# 02-_-.net
KiCad netlist of a schematic drawn in Altium Designer
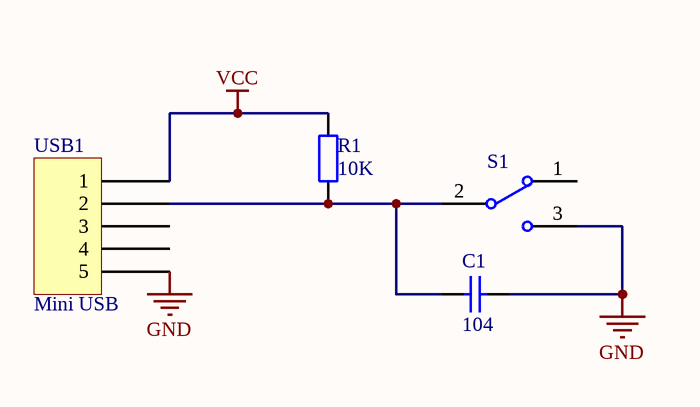
[diagram p0: 02-碰撞模块-原理图.SchDoc]

(export (version "E")
  (design (tool "Eeschema 10.0.6"))
  (components
    (comp (ref "C1")
      (value "104")
      (footprint "0805")
      (description "Capacitor")
      (fields (field (name "Comment") "Cap") (field (name "PUBLISHER") "Altium Limited"))
      (libsource (lib "Miscellaneous Devices") (part "Cap"))
    )
    (comp (ref "R1")
      (value "10K")
      (footprint "0805")
      (description "Resistor")
      (fields (field (name "Comment") "Res2") (field (name "PUBLISHER") "Altium Limited"))
      (libsource (lib "Miscellaneous Devices") (part "Res2"))
    )
    (comp (ref "S1")
      (value "SW-SPDT")
      (footprint "key")
      (description "SPDT Subminiature Toggle Switch, Right Angle Mounting, Vertical Actuation")
      (fields (field (name "PUBLISHER") "Altium Limited"))
      (libsource (lib "Miscellaneous Devices") (part "SW-SPDT"))
    )
    (comp (ref "USB1")
      (value "Mini USB")
      (footprint "USB/SM0.8-6H5")
      (libsource (lib "Schlib1") (part "Mini USB"))
    )
  )
  (nets
    (net (code "1") (name "GND") (class "Default")
      (node (ref "C1") (pin "1") (pinfunction "1_1") (pintype "passive"))
      (node (ref "S1") (pin "3") (pinfunction "3_3") (pintype "passive"))
      (node (ref "USB1") (pin "5") (pinfunction "5_5") (pintype "passive"))
    )
    (net (code "2") (name "Net-(C1-Pad2)") (class "Default")
      (node (ref "C1") (pin "2") (pinfunction "2_2") (pintype "passive"))
      (node (ref "R1") (pin "2") (pinfunction "2_2") (pintype "passive"))
      (node (ref "S1") (pin "2") (pinfunction "2_2") (pintype "passive"))
      (node (ref "USB1") (pin "2") (pinfunction "2_2") (pintype "passive"))
    )
    (net (code "3") (name "VCC") (class "Default")
      (node (ref "R1") (pin "1") (pinfunction "1_1") (pintype "passive"))
      (node (ref "USB1") (pin "1") (pinfunction "1_1") (pintype "passive"))
    )
    (net (code "4") (name "unconnected-(S1-Pad1)") (class "Default")
      (node (ref "S1") (pin "1") (pinfunction "1_1") (pintype "passive"))
    )
    (net (code "5") (name "unconnected-(USB1-Pad3)") (class "Default")
      (node (ref "USB1") (pin "3") (pinfunction "3_3") (pintype "passive"))
    )
    (net (code "6") (name "unconnected-(USB1-Pad4)") (class "Default")
      (node (ref "USB1") (pin "4") (pinfunction "4_4") (pintype "passive"))
    )
  )
)
